# temp_indicator.net
KiCad netlist of a schematic drawn in EAGLE
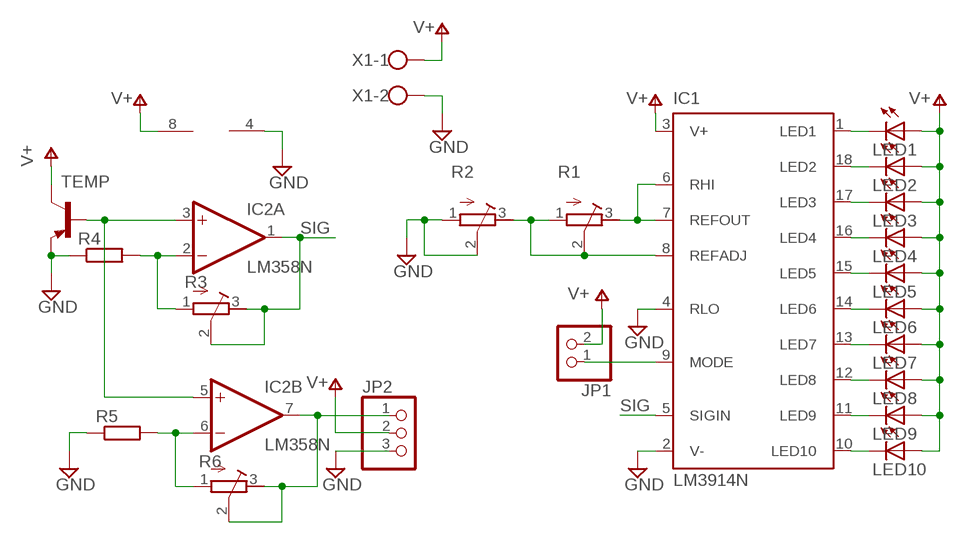
[diagram p0: schematic, sheet 1]

(export (version "E")
  (design (tool "Eeschema 10.0.6"))
  (components
    (comp (ref "IC1")
      (value "LM3914N")
      (footprint "eagle-import:DIL18")
      (libsource (lib "eagle-import") (part "LM391N4"))
    )
    (comp (ref "IC2")
      (value "LM358N")
      (footprint "eagle-import:DIL08")
      (libsource (lib "eagle-import") (part "LM358N"))
    )
    (comp (ref "JP1")
      (value "PINHD-1X2")
      (footprint "eagle-import:1X02")
      (libsource (lib "eagle-import") (part "PINHD-1X2"))
    )
    (comp (ref "JP2")
      (value "PINHD-1X3")
      (footprint "eagle-import:1X03")
      (libsource (lib "eagle-import") (part "PINHD-1X3"))
    )
    (comp (ref "LED1")
      (value "LED5MM")
      (footprint "eagle-import:LED5MM")
      (libsource (lib "eagle-import") (part "LED5MM"))
    )
    (comp (ref "LED2")
      (value "LED5MM")
      (footprint "eagle-import:LED5MM")
      (libsource (lib "eagle-import") (part "LED5MM"))
    )
    (comp (ref "LED3")
      (value "LED5MM")
      (footprint "eagle-import:LED5MM")
      (libsource (lib "eagle-import") (part "LED5MM"))
    )
    (comp (ref "LED4")
      (value "LED5MM")
      (footprint "eagle-import:LED5MM")
      (libsource (lib "eagle-import") (part "LED5MM"))
    )
    (comp (ref "LED5")
      (value "LED5MM")
      (footprint "eagle-import:LED5MM")
      (libsource (lib "eagle-import") (part "LED5MM"))
    )
    (comp (ref "LED6")
      (value "LED5MM")
      (footprint "eagle-import:LED5MM")
      (libsource (lib "eagle-import") (part "LED5MM"))
    )
    (comp (ref "LED7")
      (value "LED5MM")
      (footprint "eagle-import:LED5MM")
      (libsource (lib "eagle-import") (part "LED5MM"))
    )
    (comp (ref "LED8")
      (value "LED5MM")
      (footprint "eagle-import:LED5MM")
      (libsource (lib "eagle-import") (part "LED5MM"))
    )
    (comp (ref "LED9")
      (value "LED5MM")
      (footprint "eagle-import:LED5MM")
      (libsource (lib "eagle-import") (part "LED5MM"))
    )
    (comp (ref "LED10")
      (value "LED5MM")
      (footprint "eagle-import:LED5MM")
      (libsource (lib "eagle-import") (part "LED5MM"))
    )
    (comp (ref "R1")
      (value "R-TRIMM64W")
      (footprint "eagle-import:RTRIM64W")
      (libsource (lib "eagle-import") (part "R-TRIMM64W"))
    )
    (comp (ref "R2")
      (value "R-TRIMM64W")
      (footprint "eagle-import:RTRIM64W")
      (libsource (lib "eagle-import") (part "R-TRIMM64W"))
    )
    (comp (ref "R3")
      (value "R-TRIMM64W")
      (footprint "eagle-import:RTRIM64W")
      (libsource (lib "eagle-import") (part "R-TRIMM64W"))
    )
    (comp (ref "R4")
      (value "R-EU_0207/10")
      (footprint "eagle-import:0207_10")
      (libsource (lib "eagle-import") (part "R-EU_0207/10"))
    )
    (comp (ref "R5")
      (value "R-EU_0207/10")
      (footprint "eagle-import:0207_10")
      (libsource (lib "eagle-import") (part "R-EU_0207/10"))
    )
    (comp (ref "R6")
      (value "R-TRIMM64W")
      (footprint "eagle-import:RTRIM64W")
      (libsource (lib "eagle-import") (part "R-TRIMM64W"))
    )
    (comp (ref "TEMP")
      (value "BC557")
      (footprint "eagle-import:TO92-EBC")
      (libsource (lib "eagle-import") (part "BC557"))
    )
    (comp (ref "X1")
      (value "W237-102")
      (footprint "eagle-import:W237-102")
      (fields (field (name "MPN") "237-102"))
      (libsource (lib "eagle-import") (part "W237-102"))
    )
  )
  (nets
    (net (code "1") (name "/SIG") (class "Default")
      (node (ref "IC1") (pin "5") (pinfunction "SIGIN_5") (pintype "input"))
      (node (ref "IC2") (pin "1") (pinfunction "OUT_1") (pintype "output"))
      (node (ref "R3") (pin "2") (pinfunction "S_2") (pintype "passive"))
      (node (ref "R3") (pin "3") (pinfunction "E_3") (pintype "passive"))
    )
    (net (code "2") (name "GND") (class "Default")
      (node (ref "IC1") (pin "2") (pinfunction "V-_2") (pintype "power_in"))
      (node (ref "IC1") (pin "4") (pinfunction "RLO_4") (pintype "input"))
      (node (ref "IC2") (pin "4") (pinfunction "V-_4") (pintype "power_in"))
      (node (ref "JP2") (pin "3") (pinfunction "3_3") (pintype "passive"))
      (node (ref "R2") (pin "1") (pinfunction "A_1") (pintype "passive"))
      (node (ref "R2") (pin "2") (pinfunction "S_2") (pintype "passive"))
      (node (ref "R4") (pin "1") (pinfunction "1_1") (pintype "passive"))
      (node (ref "R5") (pin "1") (pinfunction "1_1") (pintype "passive"))
      (node (ref "TEMP") (pin "E") (pinfunction "E_E") (pintype "passive"))
      (node (ref "X1") (pin "2") (pinfunction "KL_2") (pintype "passive"))
    )
    (net (code "3") (name "Net-(IC1-LED1)") (class "Default")
      (node (ref "IC1") (pin "1") (pinfunction "LED1_1") (pintype "output"))
      (node (ref "LED1") (pin "K") (pinfunction "C_K") (pintype "passive"))
    )
    (net (code "4") (name "Net-(IC1-LED2)") (class "Default")
      (node (ref "IC1") (pin "18") (pinfunction "LED2_18") (pintype "output"))
      (node (ref "LED2") (pin "K") (pinfunction "C_K") (pintype "passive"))
    )
    (net (code "5") (name "Net-(IC1-LED3)") (class "Default")
      (node (ref "IC1") (pin "17") (pinfunction "LED3_17") (pintype "output"))
      (node (ref "LED3") (pin "K") (pinfunction "C_K") (pintype "passive"))
    )
    (net (code "6") (name "Net-(IC1-LED4)") (class "Default")
      (node (ref "IC1") (pin "16") (pinfunction "LED4_16") (pintype "output"))
      (node (ref "LED4") (pin "K") (pinfunction "C_K") (pintype "passive"))
    )
    (net (code "7") (name "Net-(IC1-LED5)") (class "Default")
      (node (ref "IC1") (pin "15") (pinfunction "LED5_15") (pintype "output"))
      (node (ref "LED5") (pin "K") (pinfunction "C_K") (pintype "passive"))
    )
    (net (code "8") (name "Net-(IC1-LED6)") (class "Default")
      (node (ref "IC1") (pin "14") (pinfunction "LED6_14") (pintype "output"))
      (node (ref "LED6") (pin "K") (pinfunction "C_K") (pintype "passive"))
    )
    (net (code "9") (name "Net-(IC1-LED7)") (class "Default")
      (node (ref "IC1") (pin "13") (pinfunction "LED7_13") (pintype "output"))
      (node (ref "LED7") (pin "K") (pinfunction "C_K") (pintype "passive"))
    )
    (net (code "10") (name "Net-(IC1-LED8)") (class "Default")
      (node (ref "IC1") (pin "12") (pinfunction "LED8_12") (pintype "output"))
      (node (ref "LED8") (pin "K") (pinfunction "C_K") (pintype "passive"))
    )
    (net (code "11") (name "Net-(IC1-LED9)") (class "Default")
      (node (ref "IC1") (pin "11") (pinfunction "LED9_11") (pintype "output"))
      (node (ref "LED9") (pin "K") (pinfunction "C_K") (pintype "passive"))
    )
    (net (code "12") (name "Net-(IC1-LED10)") (class "Default")
      (node (ref "IC1") (pin "10") (pinfunction "LED10_10") (pintype "output"))
      (node (ref "LED10") (pin "K") (pinfunction "C_K") (pintype "passive"))
    )
    (net (code "13") (name "Net-(IC1-MODE)") (class "Default")
      (node (ref "IC1") (pin "9") (pinfunction "MODE_9") (pintype "input"))
      (node (ref "JP1") (pin "1") (pinfunction "1_1") (pintype "passive"))
    )
    (net (code "14") (name "Net-(IC1-REFADJ)") (class "Default")
      (node (ref "IC1") (pin "8") (pinfunction "REFADJ_8") (pintype "passive"))
      (node (ref "R1") (pin "1") (pinfunction "A_1") (pintype "passive"))
      (node (ref "R1") (pin "2") (pinfunction "S_2") (pintype "passive"))
      (node (ref "R2") (pin "3") (pinfunction "E_3") (pintype "passive"))
    )
    (net (code "15") (name "Net-(IC1-REFOUT)") (class "Default")
      (node (ref "IC1") (pin "6") (pinfunction "RHI_6") (pintype "input"))
      (node (ref "IC1") (pin "7") (pinfunction "REFOUT_7") (pintype "output"))
      (node (ref "R1") (pin "3") (pinfunction "E_3") (pintype "passive"))
    )
    (net (code "16") (name "Net-(IC2A-+IN)") (class "Default")
      (node (ref "IC2") (pin "3") (pinfunction "+IN_3") (pintype "input"))
      (node (ref "IC2") (pin "5") (pinfunction "+IN_5") (pintype "input"))
      (node (ref "TEMP") (pin "B") (pinfunction "B_B") (pintype "passive"))
    )
    (net (code "17") (name "Net-(IC2A--IN)") (class "Default")
      (node (ref "IC2") (pin "2") (pinfunction "-IN_2") (pintype "input"))
      (node (ref "R3") (pin "1") (pinfunction "A_1") (pintype "passive"))
      (node (ref "R4") (pin "2") (pinfunction "2_2") (pintype "passive"))
    )
    (net (code "18") (name "Net-(IC2B--IN)") (class "Default")
      (node (ref "IC2") (pin "6") (pinfunction "-IN_6") (pintype "input"))
      (node (ref "R5") (pin "2") (pinfunction "2_2") (pintype "passive"))
      (node (ref "R6") (pin "1") (pinfunction "A_1") (pintype "passive"))
    )
    (net (code "19") (name "Net-(IC2B-OUT)") (class "Default")
      (node (ref "IC2") (pin "7") (pinfunction "OUT_7") (pintype "output"))
      (node (ref "JP2") (pin "1") (pinfunction "1_1") (pintype "passive"))
      (node (ref "R6") (pin "2") (pinfunction "S_2") (pintype "passive"))
      (node (ref "R6") (pin "3") (pinfunction "E_3") (pintype "passive"))
    )
    (net (code "20") (name "V+") (class "Default")
      (node (ref "IC1") (pin "3") (pinfunction "V+_3") (pintype "power_in"))
      (node (ref "IC2") (pin "8") (pinfunction "V+_8") (pintype "power_in"))
      (node (ref "JP1") (pin "2") (pinfunction "2_2") (pintype "passive"))
      (node (ref "JP2") (pin "2") (pinfunction "2_2") (pintype "passive"))
      (node (ref "LED1") (pin "A") (pinfunction "A_A") (pintype "passive"))
      (node (ref "LED10") (pin "A") (pinfunction "A_A") (pintype "passive"))
      (node (ref "LED2") (pin "A") (pinfunction "A_A") (pintype "passive"))
      (node (ref "LED3") (pin "A") (pinfunction "A_A") (pintype "passive"))
      (node (ref "LED4") (pin "A") (pinfunction "A_A") (pintype "passive"))
      (node (ref "LED5") (pin "A") (pinfunction "A_A") (pintype "passive"))
      (node (ref "LED6") (pin "A") (pinfunction "A_A") (pintype "passive"))
      (node (ref "LED7") (pin "A") (pinfunction "A_A") (pintype "passive"))
      (node (ref "LED8") (pin "A") (pinfunction "A_A") (pintype "passive"))
      (node (ref "LED9") (pin "A") (pinfunction "A_A") (pintype "passive"))
      (node (ref "TEMP") (pin "C") (pinfunction "C_C") (pintype "passive"))
      (node (ref "X1") (pin "1") (pinfunction "KL_1") (pintype "passive"))
    )
  )
)
